# control_block.net
KiCad netlist of a schematic drawn in Altium Designer
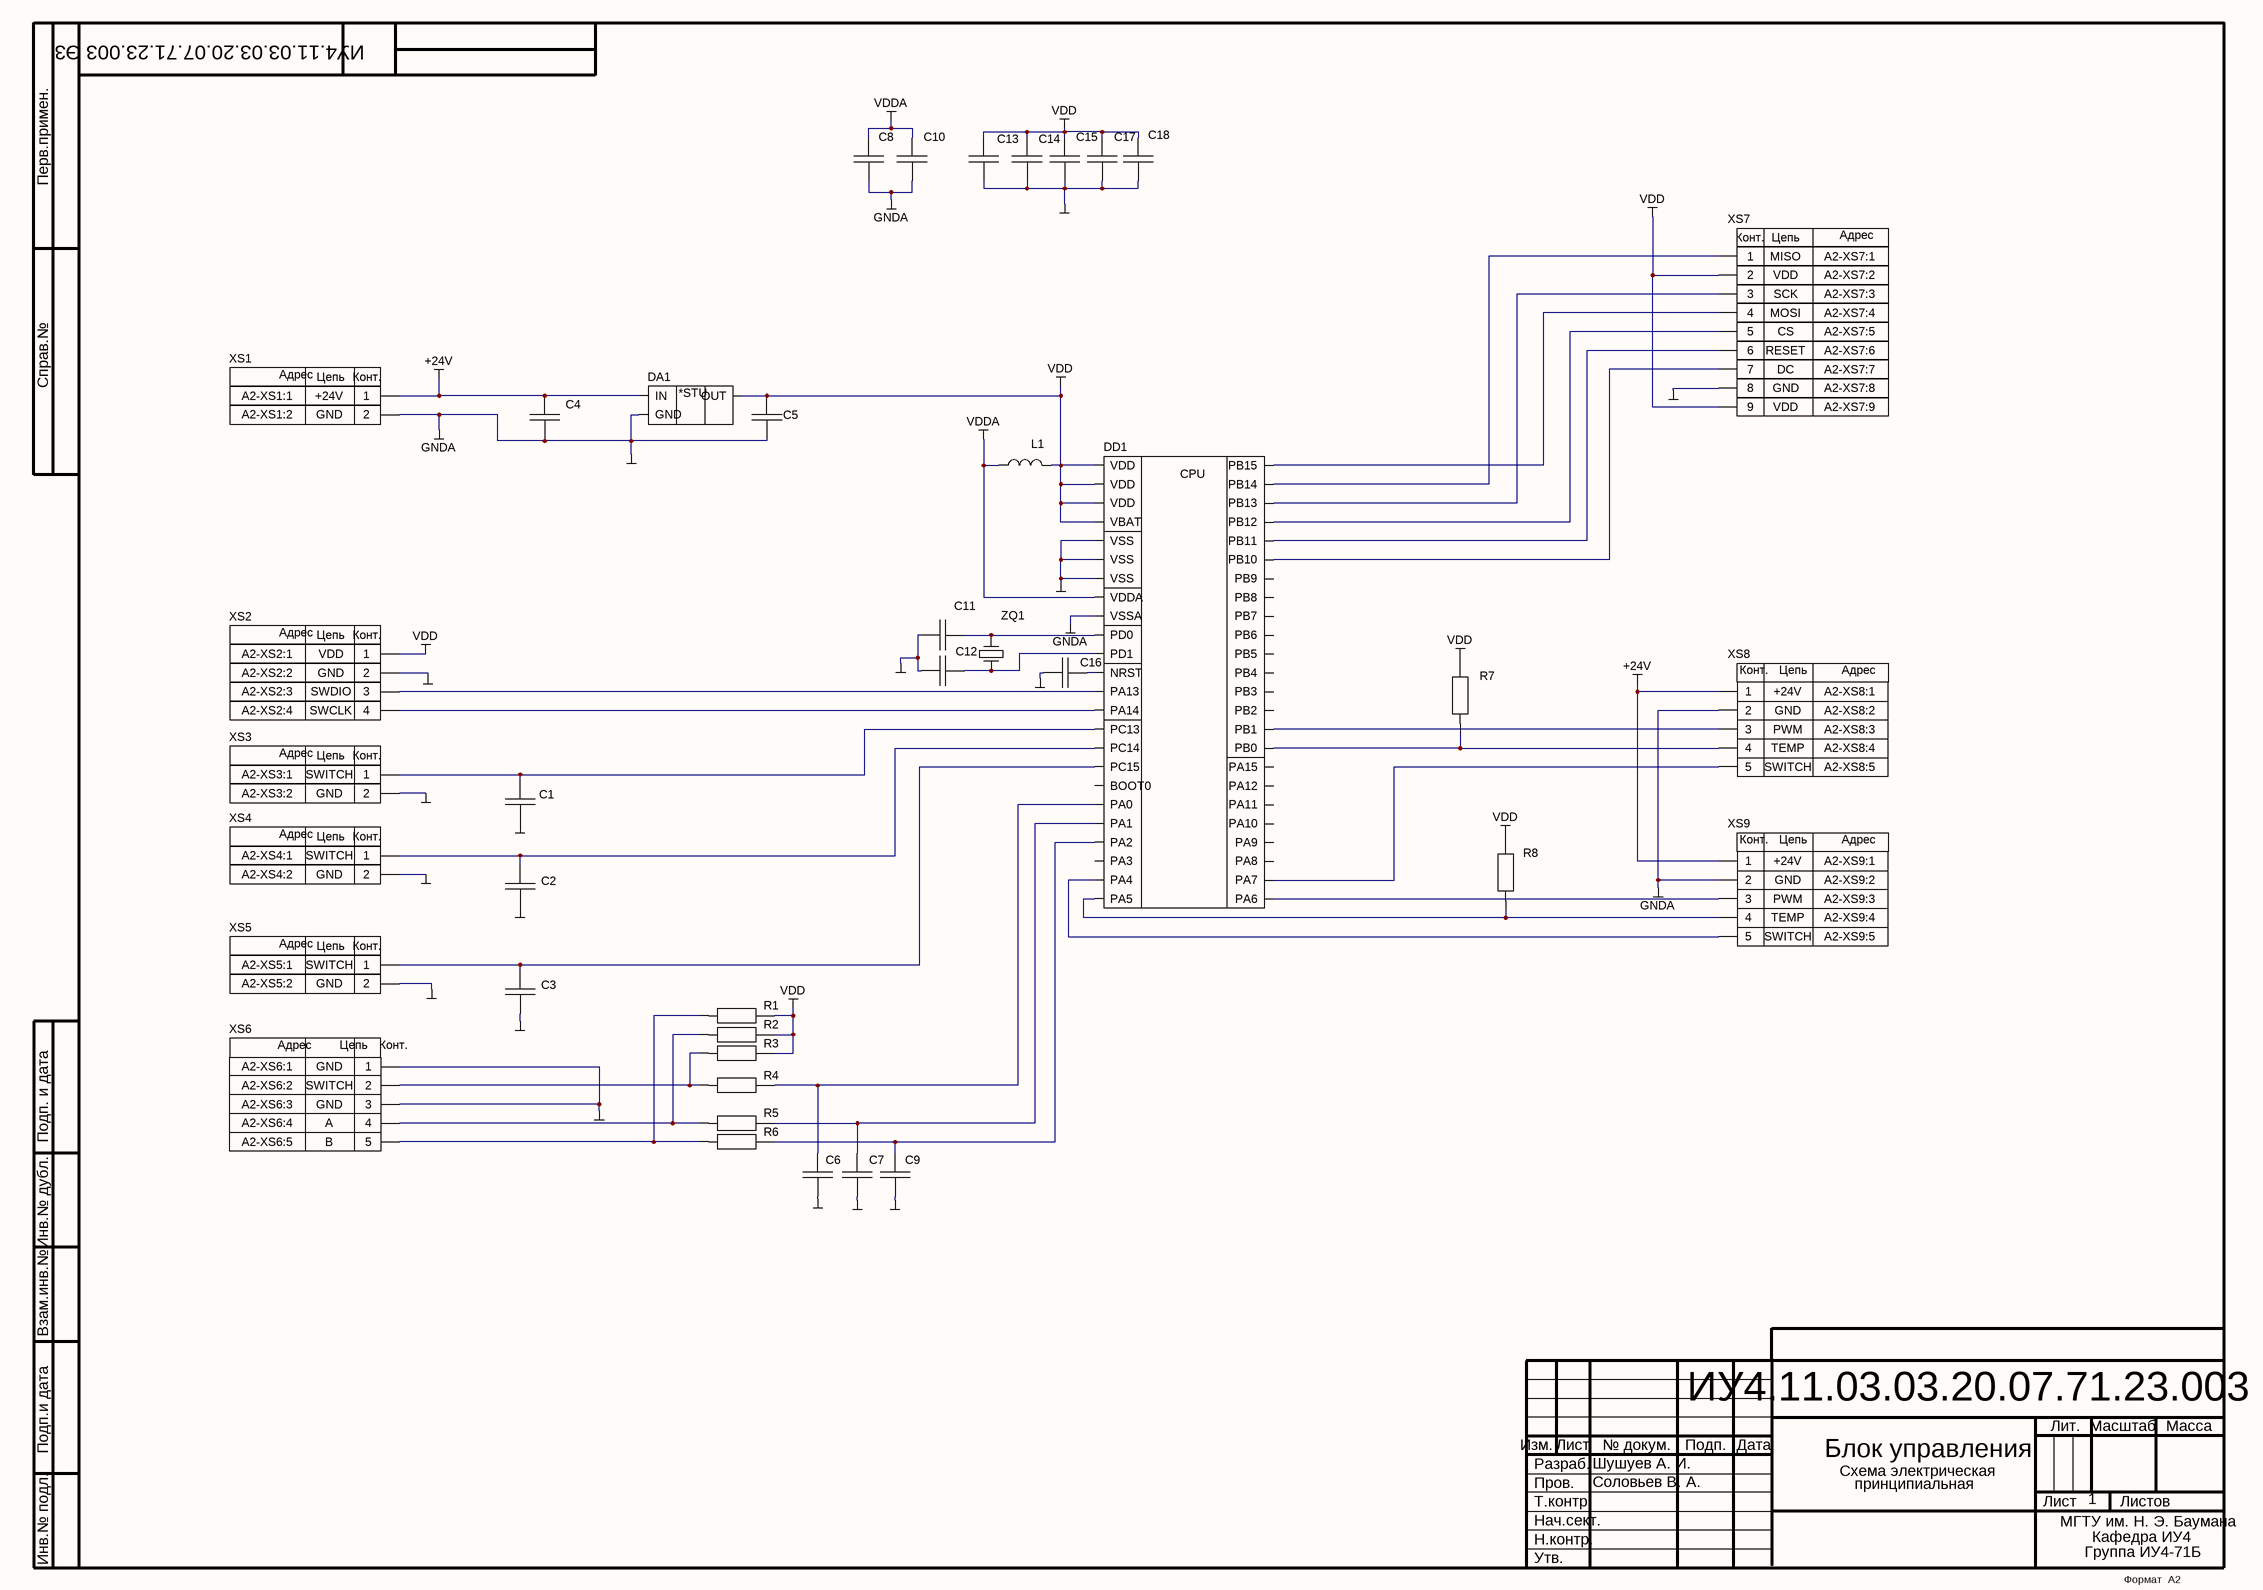
[diagram p0: control_block.SchDoc]

(export (version "E")
  (design (tool "Eeschema 10.0.6"))
  (components
    (comp (ref "C1") (value "100 нФ") (footprint "CAP: 0603") (libsource (lib "elems") (part "C_const")))
    (comp (ref "C2") (value "100 нФ") (footprint "CAP: 0603") (libsource (lib "elems") (part "C_const")))
    (comp (ref "C3") (value "100 нФ") (footprint "CAP: 0603") (libsource (lib "elems") (part "C_const")))
    (comp (ref "C4") (value "0.330 мкФ") (footprint "CAP: 0603") (libsource (lib "elems") (part "C_const")))
    (comp (ref "C5") (value "100 нФ") (footprint "CAP: 0603") (libsource (lib "elems") (part "C_const")))
    (comp (ref "C6") (value "100 нФ") (footprint "CAP: 0603") (libsource (lib "elems") (part "C_const")))
    (comp (ref "C7") (value "100 нФ") (footprint "CAP: 0603") (libsource (lib "elems") (part "C_const")))
    (comp (ref "C8") (value "1 мкФ") (footprint "CAP: 0603") (libsource (lib "elems") (part "C_const")))
    (comp (ref "C9") (value "100 нФ") (footprint "CAP: 0603") (libsource (lib "elems") (part "C_const")))
    (comp (ref "C10") (value "10 нФ") (footprint "CAP: 0603") (libsource (lib "elems") (part "C_const")))
    (comp (ref "C11") (value "22 пФ") (footprint "CAP: 0603") (libsource (lib "") (part "C_const_1")))
    (comp (ref "C12") (value "22 пФ") (footprint "CAP: 0603") (libsource (lib "") (part "C_const_2")))
    (comp (ref "C13") (value "100 нФ") (footprint "CAP: 0603") (libsource (lib "elems") (part "C_const")))
    (comp (ref "C14") (value "100 нФ") (footprint "CAP: 0603") (libsource (lib "elems") (part "C_const")))
    (comp (ref "C15") (value "100 нФ") (footprint "CAP: 0603") (libsource (lib "elems") (part "C_const")))
    (comp (ref "C16") (value "100 нФ") (footprint "CAP: 0603") (libsource (lib "elems") (part "C_const")))
    (comp (ref "C17") (value "100 нФ") (footprint "CAP: 0603") (libsource (lib "elems") (part "C_const")))
    (comp (ref "C18") (value "4.7 мкФ") (footprint "CAP: 0603") (libsource (lib "elems") (part "C_const")))
    (comp (ref "DA1") (value "78xx") (footprint "SOT89") (libsource (lib "elems") (part "78xx")))
    (comp (ref "DD1") (value "STM32F103C8T6") (libsource (lib "elems") (part "STM32F103C8T6")))
    (comp (ref "L1") (value "10 мкГн") (footprint "IND: 0805") (libsource (lib "elems") (part "L")))
    (comp (ref "R1") (value "Res") (footprint "RES: 0603") (libsource (lib "elems") (part "Res")))
    (comp (ref "R2") (value "Res") (footprint "RES: 0603") (libsource (lib "elems") (part "Res")))
    (comp (ref "R3") (value "Res") (footprint "RES: 0603") (libsource (lib "elems") (part "Res")))
    (comp (ref "R4") (value "Res") (footprint "RES: 0603") (libsource (lib "elems") (part "Res")))
    (comp (ref "R5") (value "Res") (footprint "RES: 0603") (libsource (lib "elems") (part "Res")))
    (comp (ref "R6") (value "Res") (footprint "RES: 0603") (libsource (lib "elems") (part "Res")))
    (comp (ref "R7") (value "Res") (footprint "RES: 1206") (libsource (lib "elems") (part "Res")))
    (comp (ref "R8") (value "Res") (footprint "RES: 1206") (libsource (lib "elems") (part "Res")))
    (comp (ref "XS1")
      (value "X2")
      (footprint "CON: WF-02")
      (fields
        (field (name "CIRCUIT2") "GND")
        (field (name "CIRCUIT1") "+24V")
        (field (name "=ADDRESS2") "A2-XS1:2")
        (field (name "=ADDRESS1") "A2-XS1:1")
      )
      (libsource (lib "elems") (part "X2"))
    )
    (comp (ref "XS2")
      (value "X4")
      (footprint "CON: WF-04")
      (fields
        (field (name "CIRCUIT2") "GND")
        (field (name "CIRCUIT3") "SWDIO")
        (field (name "CIRCUIT1") "VDD")
        (field (name "CIRCUIT4") "SWCLK")
        (field (name "=ADDRESS4") "A2-XS2:4")
        (field (name "=ADDRESS3") "A2-XS2:3")
        (field (name "=ADDRESS2") "A2-XS2:2")
        (field (name "=ADDRESS1") "A2-XS2:1")
      )
      (libsource (lib "elems") (part "X4"))
    )
    (comp (ref "XS3")
      (value "X2")
      (footprint "CON: WF-02")
      (fields
        (field (name "CIRCUIT2") "GND")
        (field (name "CIRCUIT1") "SWITCH")
        (field (name "=ADDRESS2") "A2-XS3:2")
        (field (name "=ADDRESS1") "A2-XS3:1")
      )
      (libsource (lib "elems") (part "X2"))
    )
    (comp (ref "XS4")
      (value "X2")
      (footprint "CON: WF-02")
      (fields
        (field (name "CIRCUIT2") "GND")
        (field (name "CIRCUIT1") "SWITCH")
        (field (name "=ADDRESS2") "A2-XS4:2")
        (field (name "=ADDRESS1") "A2-XS4:1")
      )
      (libsource (lib "elems") (part "X2"))
    )
    (comp (ref "XS5")
      (value "X2")
      (footprint "CON: WF-02")
      (fields
        (field (name "CIRCUIT2") "GND")
        (field (name "CIRCUIT1") "SWITCH")
        (field (name "=ADDRESS2") "A2-XS5:2")
        (field (name "=ADDRESS1") "A2-XS5:1")
      )
      (libsource (lib "elems") (part "X2"))
    )
    (comp (ref "XS6")
      (value "X5")
      (footprint "CON: CWF-5")
      (fields
        (field (name "CIRTUIT5") "B")
        (field (name "CIRCUIT4") "A")
        (field (name "CIRCUIT3") "GND")
        (field (name "CIRCUIT2") "SWITCH")
        (field (name "CIRCUIT1") "GND")
        (field (name "=ADDRESS5") "A2-XS6:5")
        (field (name "=ADDRESS4") "A2-XS6:4")
        (field (name "=ADDRESS3") "A2-XS6:3")
        (field (name "=ADDRESS2") "A2-XS6:2")
        (field (name "=ADDRESS1") "A2-XS6:1")
      )
      (libsource (lib "elems") (part "X5"))
    )
    (comp (ref "XS7")
      (value "X9")
      (footprint "CON: IDC-10MS")
      (fields
        (field (name "CIRCTUIT9") "VDD")
        (field (name "CIRCTUIT8") "GND")
        (field (name "CIRCTUIT7") "DC")
        (field (name "CIRCTUIT6") "RESET")
        (field (name "CIRCTUIT5") "CS")
        (field (name "CIRCTUIT4") "MOSI")
        (field (name "CIRCTUIT3") "SCK")
        (field (name "CIRCTUIT2") "VDD")
        (field (name "CIRCTUIT1") "MISO")
        (field (name "=ADDRESS9") "A2-XS7:9")
        (field (name "=ADDRESS8") "A2-XS7:8")
        (field (name "=ADDRESS7") "A2-XS7:7")
        (field (name "=ADDRESS5") "A2-XS7:5")
        (field (name "=ADDRESS6") "A2-XS7:6")
        (field (name "=ADDRESS4") "A2-XS7:4")
        (field (name "=ADDRESS3") "A2-XS7:3")
        (field (name "=ADDRESS2") "A2-XS7:2")
        (field (name "=ADDRESS1") "A2-XS7:1")
      )
      (libsource (lib "elems") (part "X9"))
    )
    (comp (ref "XS8")
      (value "X5")
      (footprint "CON: CWF-5")
      (fields
        (field (name "CIRTUIT5") "SWITCH")
        (field (name "CIRCUIT4") "TEMP")
        (field (name "CIRCUIT3") "PWM")
        (field (name "CIRCUIT2") "GND")
        (field (name "CIRCUIT1") "+24V")
        (field (name "=ADDRESS5") "A2-XS8:5")
        (field (name "=ADDRESS4") "A2-XS8:4")
        (field (name "=ADDRESS3") "A2-XS8:3")
        (field (name "=ADDRESS2") "A2-XS8:2")
        (field (name "=ADDRESS1") "A2-XS8:1")
      )
      (libsource (lib "elems") (part "X5"))
    )
    (comp (ref "XS9")
      (value "X5")
      (footprint "CON: CWF-5")
      (fields
        (field (name "CIRTUIT5") "SWITCH")
        (field (name "CIRCUIT4") "TEMP")
        (field (name "CIRCUIT3") "PWM")
        (field (name "CIRCUIT2") "GND")
        (field (name "CIRCUIT1") "+24V")
        (field (name "=ADDRESS5") "A2-XS9:5")
        (field (name "=ADDRESS4") "A2-XS9:4")
        (field (name "=ADDRESS3") "A2-XS9:3")
        (field (name "=ADDRESS2") "A2-XS9:2")
        (field (name "=ADDRESS1") "A2-XS9:1")
      )
      (libsource (lib "elems") (part "X5"))
    )
    (comp (ref "ZQ1") (value "AT-41CD2-8MHz") (footprint "AT-41CD2") (libsource (lib "elems") (part "ZQ")))
  )
  (nets
    (net (code "1") (name "+24V") (class "Default")
      (node (ref "C4") (pin "2") (pinfunction "2_2") (pintype "passive"))
      (node (ref "DA1") (pin "1") (pinfunction "IN_1") (pintype "passive"))
      (node (ref "XS1") (pin "1") (pinfunction "1_1") (pintype "passive"))
      (node (ref "XS8") (pin "1") (pinfunction "1_1") (pintype "passive"))
      (node (ref "XS9") (pin "1") (pinfunction "1_1") (pintype "passive"))
    )
    (net (code "2") (name "GND") (class "Default")
      (node (ref "C1") (pin "1") (pinfunction "1_1") (pintype "passive"))
      (node (ref "C10") (pin "1") (pinfunction "1_1") (pintype "passive"))
      (node (ref "C11") (pin "1") (pinfunction "1_1") (pintype "passive"))
      (node (ref "C12") (pin "1") (pinfunction "1_1") (pintype "passive"))
      (node (ref "C13") (pin "1") (pinfunction "1_1") (pintype "passive"))
      (node (ref "C14") (pin "1") (pinfunction "1_1") (pintype "passive"))
      (node (ref "C15") (pin "1") (pinfunction "1_1") (pintype "passive"))
      (node (ref "C16") (pin "1") (pinfunction "1_1") (pintype "passive"))
      (node (ref "C17") (pin "1") (pinfunction "1_1") (pintype "passive"))
      (node (ref "C18") (pin "1") (pinfunction "1_1") (pintype "passive"))
      (node (ref "C2") (pin "1") (pinfunction "1_1") (pintype "passive"))
      (node (ref "C3") (pin "1") (pinfunction "1_1") (pintype "passive"))
      (node (ref "C4") (pin "1") (pinfunction "1_1") (pintype "passive"))
      (node (ref "C5") (pin "1") (pinfunction "1_1") (pintype "passive"))
      (node (ref "C6") (pin "1") (pinfunction "1_1") (pintype "passive"))
      (node (ref "C7") (pin "1") (pinfunction "1_1") (pintype "passive"))
      (node (ref "C8") (pin "1") (pinfunction "1_1") (pintype "passive"))
      (node (ref "C9") (pin "1") (pinfunction "1_1") (pintype "passive"))
      (node (ref "DA1") (pin "3") (pinfunction "GND_3") (pintype "passive"))
      (node (ref "DD1") (pin "23") (pinfunction "VSS_23") (pintype "passive"))
      (node (ref "DD1") (pin "35") (pinfunction "VSS_35") (pintype "passive"))
      (node (ref "DD1") (pin "47") (pinfunction "VSS_47") (pintype "passive"))
      (node (ref "DD1") (pin "8") (pinfunction "VSSA_8") (pintype "passive"))
      (node (ref "XS1") (pin "2") (pinfunction "2_2") (pintype "passive"))
      (node (ref "XS2") (pin "2") (pinfunction "2_2") (pintype "passive"))
      (node (ref "XS3") (pin "2") (pinfunction "2_2") (pintype "passive"))
      (node (ref "XS4") (pin "2") (pinfunction "2_2") (pintype "passive"))
      (node (ref "XS5") (pin "2") (pinfunction "2_2") (pintype "passive"))
      (node (ref "XS6") (pin "1") (pinfunction "1_1") (pintype "passive"))
      (node (ref "XS6") (pin "3") (pinfunction "3_3") (pintype "passive"))
      (node (ref "XS7") (pin "8") (pinfunction "8_8") (pintype "passive"))
      (node (ref "XS8") (pin "2") (pinfunction "2_2") (pintype "passive"))
      (node (ref "XS9") (pin "2") (pinfunction "2_2") (pintype "passive"))
    )
    (net (code "3") (name "Net-(DD1-NRST)") (class "Default")
      (node (ref "C16") (pin "2") (pinfunction "2_2") (pintype "passive"))
      (node (ref "DD1") (pin "7") (pinfunction "NRST_7") (pintype "passive"))
    )
    (net (code "4") (name "Net-(DD1-PA0)") (class "Default")
      (node (ref "C6") (pin "2") (pinfunction "2_2") (pintype "passive"))
      (node (ref "DD1") (pin "10") (pinfunction "PA0_10") (pintype "passive"))
      (node (ref "R4") (pin "2") (pinfunction "6_2") (pintype "passive"))
    )
    (net (code "5") (name "Net-(DD1-PA1)") (class "Default")
      (node (ref "C7") (pin "2") (pinfunction "2_2") (pintype "passive"))
      (node (ref "DD1") (pin "11") (pinfunction "PA1_11") (pintype "passive"))
      (node (ref "R5") (pin "2") (pinfunction "6_2") (pintype "passive"))
    )
    (net (code "6") (name "Net-(DD1-PA2)") (class "Default")
      (node (ref "C9") (pin "2") (pinfunction "2_2") (pintype "passive"))
      (node (ref "DD1") (pin "12") (pinfunction "PA2_12") (pintype "passive"))
      (node (ref "R6") (pin "2") (pinfunction "6_2") (pintype "passive"))
    )
    (net (code "7") (name "Net-(DD1-PA4)") (class "Default")
      (node (ref "DD1") (pin "14") (pinfunction "PA4_14") (pintype "passive"))
      (node (ref "XS9") (pin "5") (pinfunction "5_5") (pintype "passive"))
    )
    (net (code "8") (name "Net-(DD1-PA5)") (class "Default")
      (node (ref "DD1") (pin "15") (pinfunction "PA5_15") (pintype "passive"))
      (node (ref "R8") (pin "1") (pinfunction "1_1") (pintype "passive"))
      (node (ref "XS9") (pin "4") (pinfunction "4_4") (pintype "passive"))
    )
    (net (code "9") (name "Net-(DD1-PA6)") (class "Default")
      (node (ref "DD1") (pin "16") (pinfunction "PA6_16") (pintype "passive"))
      (node (ref "XS9") (pin "3") (pinfunction "3_3") (pintype "passive"))
    )
    (net (code "10") (name "Net-(DD1-PA7)") (class "Default")
      (node (ref "DD1") (pin "17") (pinfunction "PA7_17") (pintype "passive"))
      (node (ref "XS8") (pin "5") (pinfunction "5_5") (pintype "passive"))
    )
    (net (code "11") (name "Net-(DD1-PA13)") (class "Default")
      (node (ref "DD1") (pin "34") (pinfunction "PA13_34") (pintype "passive"))
      (node (ref "XS2") (pin "3") (pinfunction "3_3") (pintype "passive"))
    )
    (net (code "12") (name "Net-(DD1-PA14)") (class "Default")
      (node (ref "DD1") (pin "37") (pinfunction "PA14_37") (pintype "passive"))
      (node (ref "XS2") (pin "4") (pinfunction "4_4") (pintype "passive"))
    )
    (net (code "13") (name "Net-(DD1-PB0)") (class "Default")
      (node (ref "DD1") (pin "18") (pinfunction "PB0_18") (pintype "passive"))
      (node (ref "R7") (pin "1") (pinfunction "1_1") (pintype "passive"))
      (node (ref "XS8") (pin "4") (pinfunction "4_4") (pintype "passive"))
    )
    (net (code "14") (name "Net-(DD1-PB1)") (class "Default")
      (node (ref "DD1") (pin "19") (pinfunction "PB1_19") (pintype "passive"))
      (node (ref "XS8") (pin "3") (pinfunction "3_3") (pintype "passive"))
    )
    (net (code "15") (name "Net-(DD1-PB10)") (class "Default")
      (node (ref "DD1") (pin "21") (pinfunction "PB10_21") (pintype "passive"))
      (node (ref "XS7") (pin "7") (pinfunction "7_7") (pintype "passive"))
    )
    (net (code "16") (name "Net-(DD1-PB11)") (class "Default")
      (node (ref "DD1") (pin "22") (pinfunction "PB11_22") (pintype "passive"))
      (node (ref "XS7") (pin "6") (pinfunction "6_6") (pintype "passive"))
    )
    (net (code "17") (name "Net-(DD1-PB12)") (class "Default")
      (node (ref "DD1") (pin "25") (pinfunction "PB12_25") (pintype "passive"))
      (node (ref "XS7") (pin "5") (pinfunction "5_5") (pintype "passive"))
    )
    (net (code "18") (name "Net-(DD1-PB13)") (class "Default")
      (node (ref "DD1") (pin "26") (pinfunction "PB13_26") (pintype "passive"))
      (node (ref "XS7") (pin "3") (pinfunction "3_3") (pintype "passive"))
    )
    (net (code "19") (name "Net-(DD1-PB14)") (class "Default")
      (node (ref "DD1") (pin "27") (pinfunction "PB14_27") (pintype "passive"))
      (node (ref "XS7") (pin "1") (pinfunction "1_1") (pintype "passive"))
    )
    (net (code "20") (name "Net-(DD1-PB15)") (class "Default")
      (node (ref "DD1") (pin "28") (pinfunction "PB15_28") (pintype "passive"))
      (node (ref "XS7") (pin "4") (pinfunction "4_4") (pintype "passive"))
    )
    (net (code "21") (name "Net-(DD1-PC13)") (class "Default")
      (node (ref "C1") (pin "2") (pinfunction "2_2") (pintype "passive"))
      (node (ref "DD1") (pin "2") (pinfunction "PC13_2") (pintype "passive"))
      (node (ref "XS3") (pin "1") (pinfunction "1_1") (pintype "passive"))
    )
    (net (code "22") (name "Net-(DD1-PC14)") (class "Default")
      (node (ref "C2") (pin "2") (pinfunction "2_2") (pintype "passive"))
      (node (ref "DD1") (pin "3") (pinfunction "PC14_3") (pintype "passive"))
      (node (ref "XS4") (pin "1") (pinfunction "1_1") (pintype "passive"))
    )
    (net (code "23") (name "Net-(DD1-PC15)") (class "Default")
      (node (ref "C3") (pin "2") (pinfunction "2_2") (pintype "passive"))
      (node (ref "DD1") (pin "4") (pinfunction "PC15_4") (pintype "passive"))
      (node (ref "XS5") (pin "1") (pinfunction "1_1") (pintype "passive"))
    )
    (net (code "24") (name "Net-(DD1-PD0)") (class "Default")
      (node (ref "C11") (pin "2") (pinfunction "2_2") (pintype "passive"))
      (node (ref "DD1") (pin "5") (pinfunction "PD0_5") (pintype "passive"))
      (node (ref "ZQ1") (pin "2") (pinfunction "2_2") (pintype "passive"))
    )
    (net (code "25") (name "Net-(DD1-PD1)") (class "Default")
      (node (ref "C12") (pin "2") (pinfunction "2_2") (pintype "passive"))
      (node (ref "DD1") (pin "6") (pinfunction "PD1_6") (pintype "passive"))
      (node (ref "ZQ1") (pin "1") (pinfunction "1_1") (pintype "passive"))
    )
    (net (code "26") (name "Net-(R1-Pad1)") (class "Default")
      (node (ref "R1") (pin "1") (pinfunction "1_1") (pintype "passive"))
      (node (ref "R6") (pin "1") (pinfunction "1_1") (pintype "passive"))
      (node (ref "XS6") (pin "5") (pinfunction "5_5") (pintype "passive"))
    )
    (net (code "27") (name "Net-(R2-Pad1)") (class "Default")
      (node (ref "R2") (pin "1") (pinfunction "1_1") (pintype "passive"))
      (node (ref "R5") (pin "1") (pinfunction "1_1") (pintype "passive"))
      (node (ref "XS6") (pin "4") (pinfunction "4_4") (pintype "passive"))
    )
    (net (code "28") (name "Net-(R3-Pad1)") (class "Default")
      (node (ref "R3") (pin "1") (pinfunction "1_1") (pintype "passive"))
      (node (ref "R4") (pin "1") (pinfunction "1_1") (pintype "passive"))
      (node (ref "XS6") (pin "2") (pinfunction "2_2") (pintype "passive"))
    )
    (net (code "29") (name "VDD") (class "Default")
      (node (ref "C13") (pin "2") (pinfunction "2_2") (pintype "passive"))
      (node (ref "C14") (pin "2") (pinfunction "2_2") (pintype "passive"))
      (node (ref "C15") (pin "2") (pinfunction "2_2") (pintype "passive"))
      (node (ref "C17") (pin "2") (pinfunction "2_2") (pintype "passive"))
      (node (ref "C18") (pin "2") (pinfunction "2_2") (pintype "passive"))
      (node (ref "C5") (pin "2") (pinfunction "2_2") (pintype "passive"))
      (node (ref "DA1") (pin "2") (pinfunction "OUT_2") (pintype "passive"))
      (node (ref "DD1") (pin "1") (pinfunction "VBAT_1") (pintype "passive"))
      (node (ref "DD1") (pin "24") (pinfunction "VDD_24") (pintype "passive"))
      (node (ref "DD1") (pin "36") (pinfunction "VDD_36") (pintype "passive"))
      (node (ref "DD1") (pin "48") (pinfunction "VDD_48") (pintype "passive"))
      (node (ref "L1") (pin "2") (pinfunction "2_2") (pintype "passive"))
      (node (ref "R1") (pin "2") (pinfunction "6_2") (pintype "passive"))
      (node (ref "R2") (pin "2") (pinfunction "6_2") (pintype "passive"))
      (node (ref "R3") (pin "2") (pinfunction "6_2") (pintype "passive"))
      (node (ref "R7") (pin "2") (pinfunction "6_2") (pintype "passive"))
      (node (ref "R8") (pin "2") (pinfunction "6_2") (pintype "passive"))
      (node (ref "XS2") (pin "1") (pinfunction "1_1") (pintype "passive"))
      (node (ref "XS7") (pin "2") (pinfunction "2_2") (pintype "passive"))
      (node (ref "XS7") (pin "9") (pinfunction "9_9") (pintype "passive"))
    )
    (net (code "30") (name "VDDA") (class "Default")
      (node (ref "C10") (pin "2") (pinfunction "2_2") (pintype "passive"))
      (node (ref "C8") (pin "2") (pinfunction "2_2") (pintype "passive"))
      (node (ref "DD1") (pin "9") (pinfunction "VDDA_9") (pintype "passive"))
      (node (ref "L1") (pin "1") (pinfunction "1_1") (pintype "passive"))
    )
    (net (code "31") (name "unconnected-(DD1-BOOT0-Pad44)") (class "Default")
      (node (ref "DD1") (pin "44") (pinfunction "BOOT0_44") (pintype "passive"))
    )
    (net (code "32") (name "unconnected-(DD1-PA3-Pad13)") (class "Default")
      (node (ref "DD1") (pin "13") (pinfunction "PA3_13") (pintype "passive"))
    )
    (net (code "33") (name "unconnected-(DD1-PA8-Pad29)") (class "Default")
      (node (ref "DD1") (pin "29") (pinfunction "PA8_29") (pintype "passive"))
    )
    (net (code "34") (name "unconnected-(DD1-PA9-Pad30)") (class "Default")
      (node (ref "DD1") (pin "30") (pinfunction "PA9_30") (pintype "passive"))
    )
    (net (code "35") (name "unconnected-(DD1-PA10-Pad31)") (class "Default")
      (node (ref "DD1") (pin "31") (pinfunction "PA10_31") (pintype "passive"))
    )
    (net (code "36") (name "unconnected-(DD1-PA11-Pad32)") (class "Default")
      (node (ref "DD1") (pin "32") (pinfunction "PA11_32") (pintype "passive"))
    )
    (net (code "37") (name "unconnected-(DD1-PA12-Pad33)") (class "Default")
      (node (ref "DD1") (pin "33") (pinfunction "PA12_33") (pintype "passive"))
    )
    (net (code "38") (name "unconnected-(DD1-PA15-Pad38)") (class "Default")
      (node (ref "DD1") (pin "38") (pinfunction "PA15_38") (pintype "passive"))
    )
    (net (code "39") (name "unconnected-(DD1-PB2-Pad20)") (class "Default")
      (node (ref "DD1") (pin "20") (pinfunction "PB2_20") (pintype "passive"))
    )
    (net (code "40") (name "unconnected-(DD1-PB3-Pad39)") (class "Default")
      (node (ref "DD1") (pin "39") (pinfunction "PB3_39") (pintype "passive"))
    )
    (net (code "41") (name "unconnected-(DD1-PB4-Pad40)") (class "Default")
      (node (ref "DD1") (pin "40") (pinfunction "PB4_40") (pintype "passive"))
    )
    (net (code "42") (name "unconnected-(DD1-PB5-Pad41)") (class "Default")
      (node (ref "DD1") (pin "41") (pinfunction "PB5_41") (pintype "passive"))
    )
    (net (code "43") (name "unconnected-(DD1-PB6-Pad42)") (class "Default")
      (node (ref "DD1") (pin "42") (pinfunction "PB6_42") (pintype "passive"))
    )
    (net (code "44") (name "unconnected-(DD1-PB7-Pad43)") (class "Default")
      (node (ref "DD1") (pin "43") (pinfunction "PB7_43") (pintype "passive"))
    )
    (net (code "45") (name "unconnected-(DD1-PB8-Pad45)") (class "Default")
      (node (ref "DD1") (pin "45") (pinfunction "PB8_45") (pintype "passive"))
    )
    (net (code "46") (name "unconnected-(DD1-PB9-Pad46)") (class "Default")
      (node (ref "DD1") (pin "46") (pinfunction "PB9_46") (pintype "passive"))
    )
  )
)
